# prototype2-only-bot-ground-plane.net
KiCad netlist of a schematic drawn in EAGLE
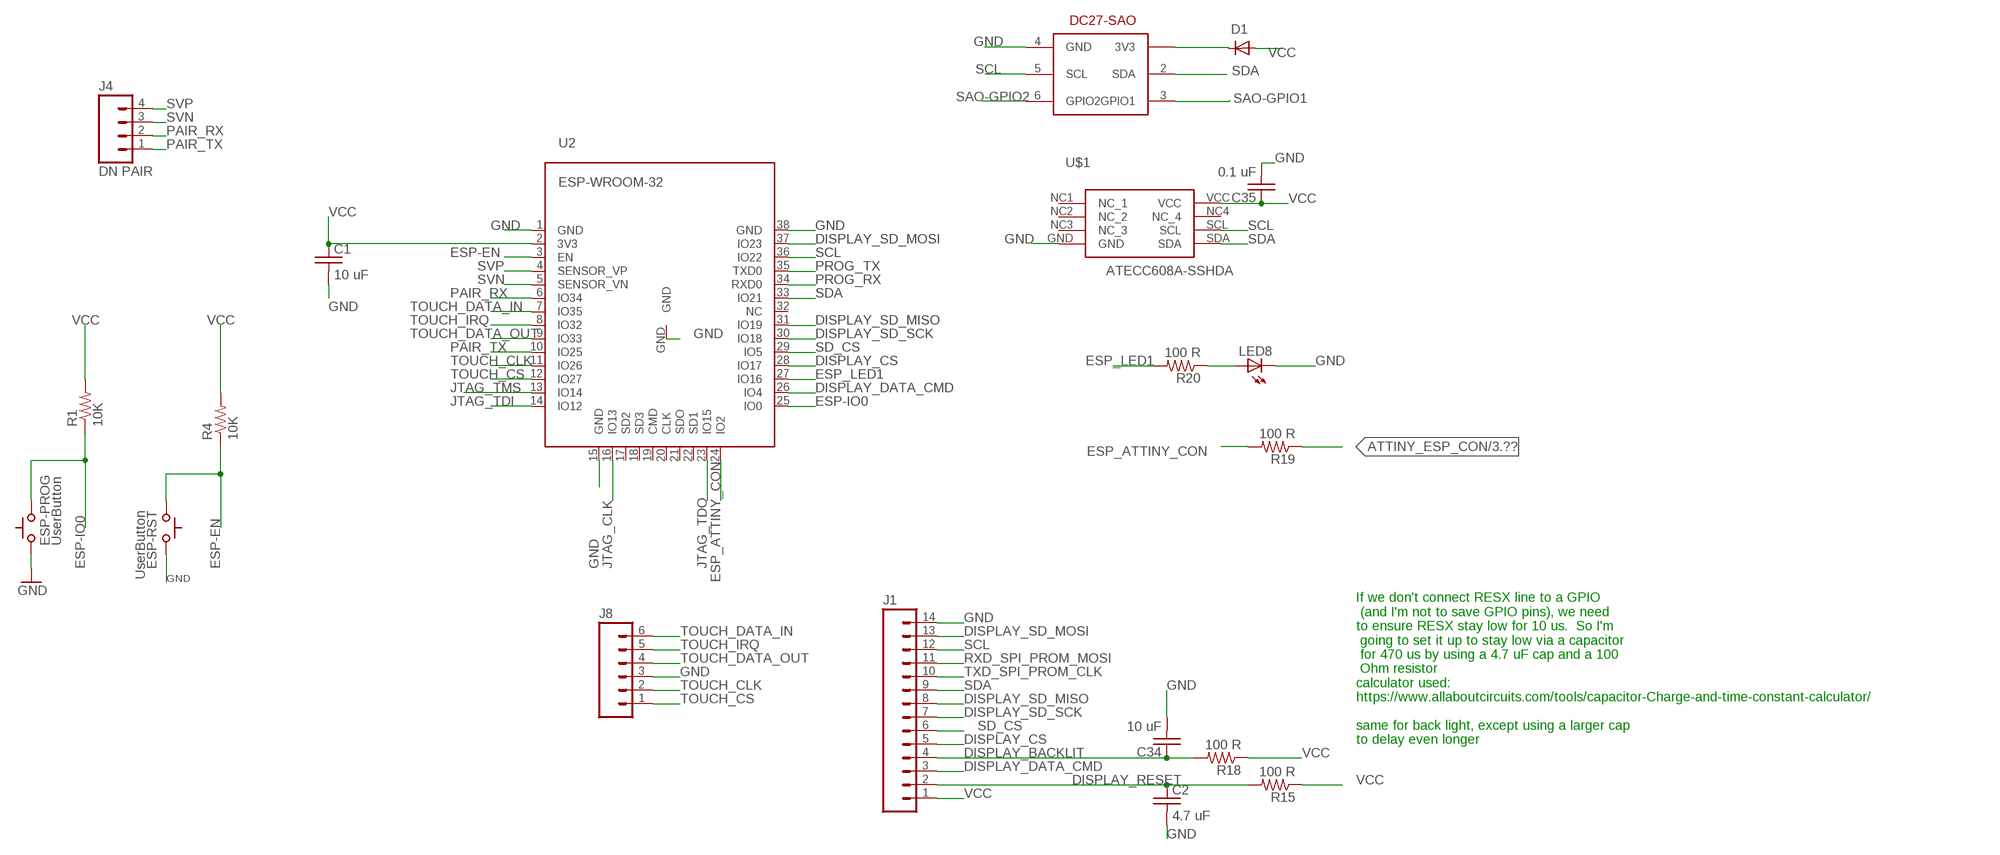
[diagram p0: schematic, sheet 1]
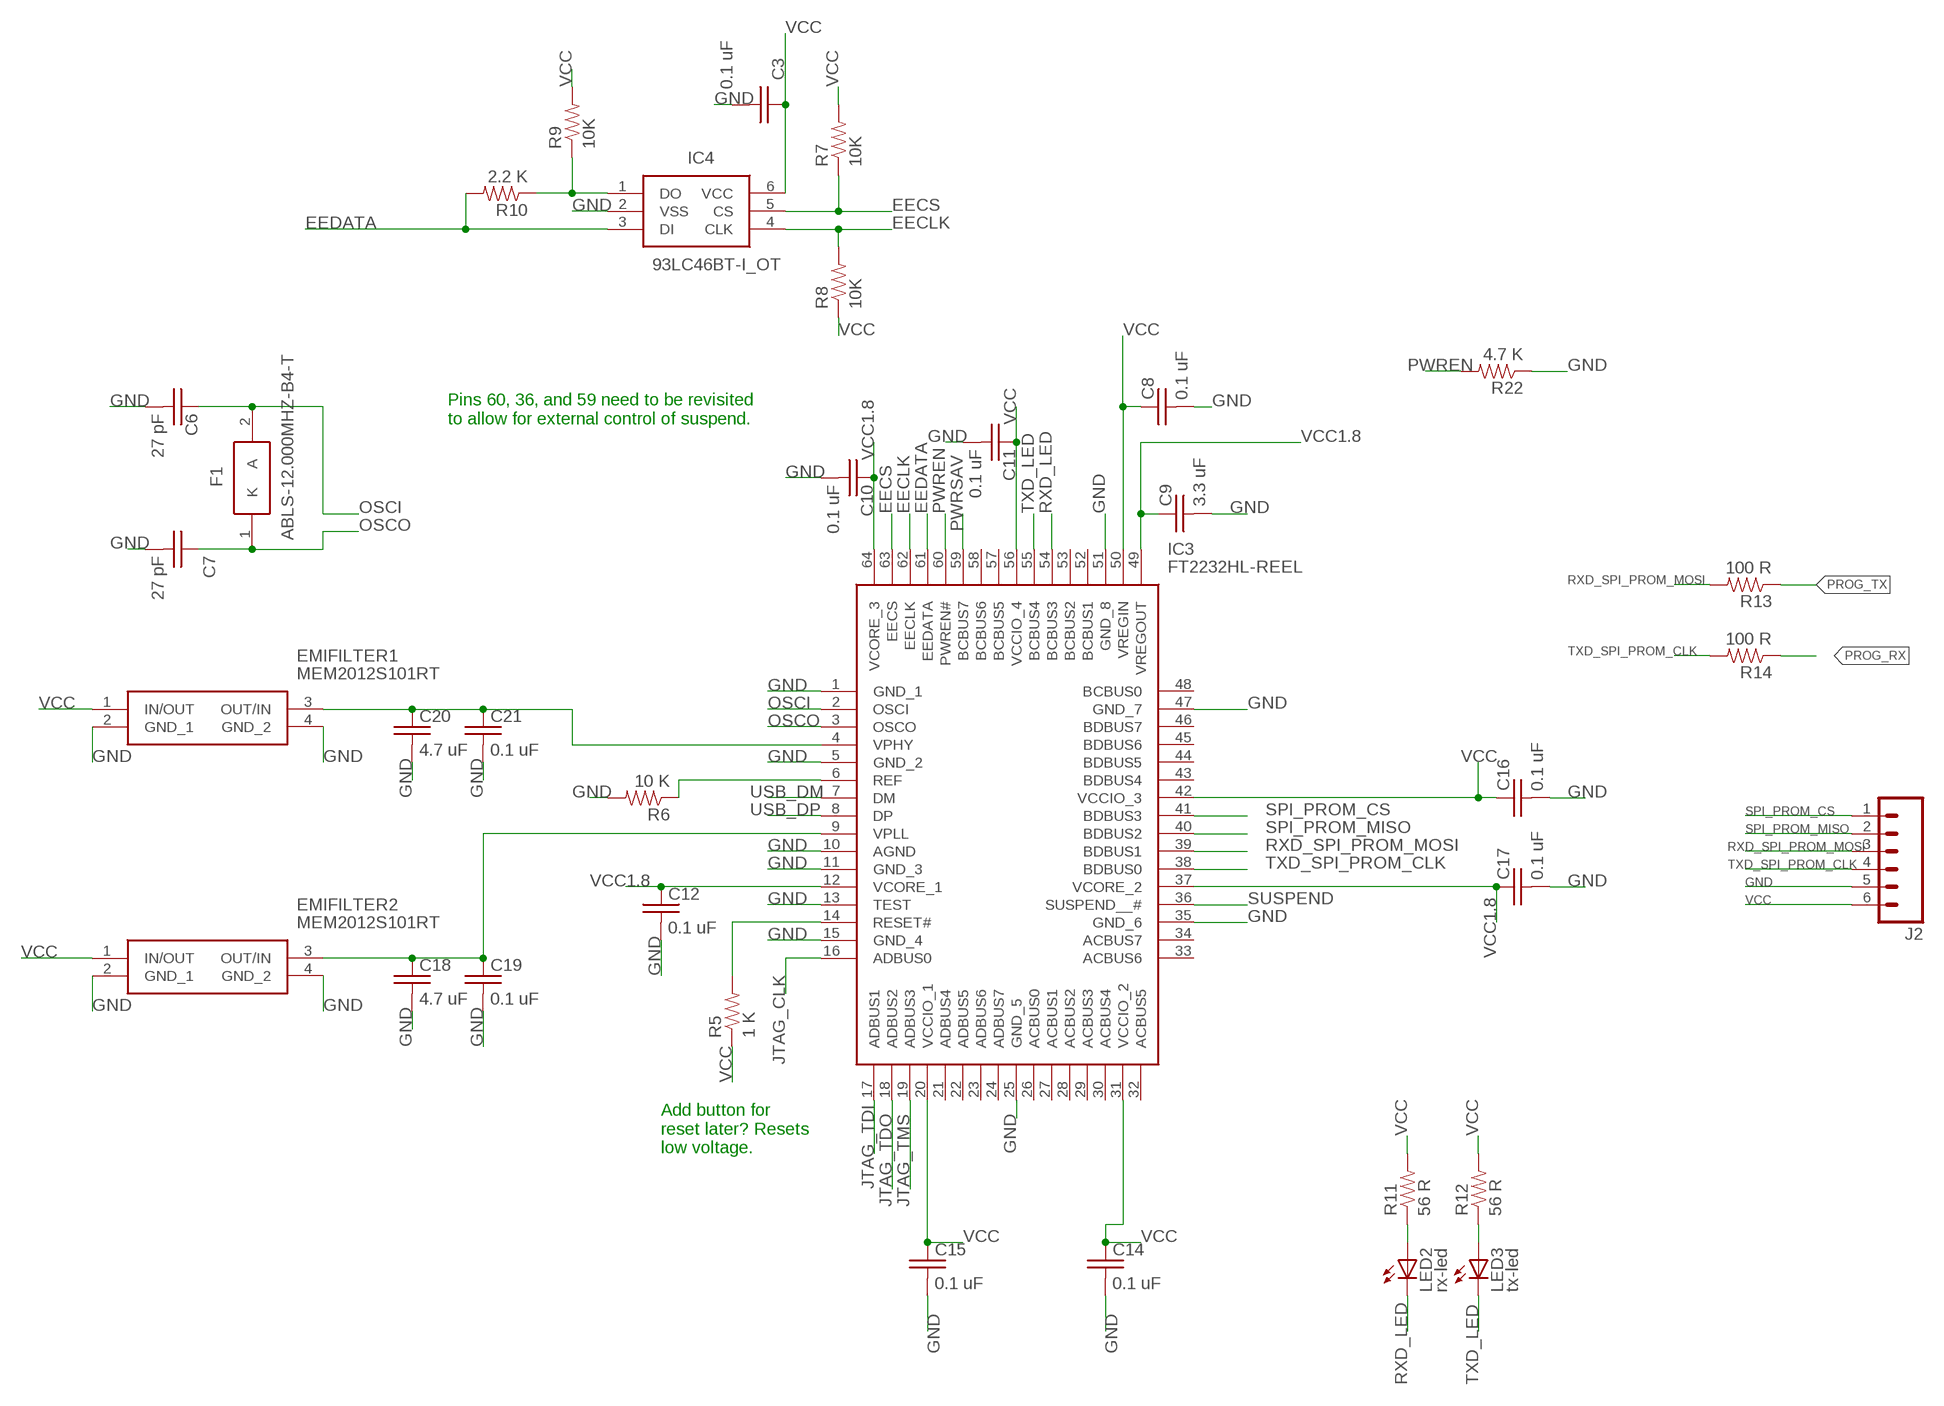
[diagram p1: schematic, sheet 2]
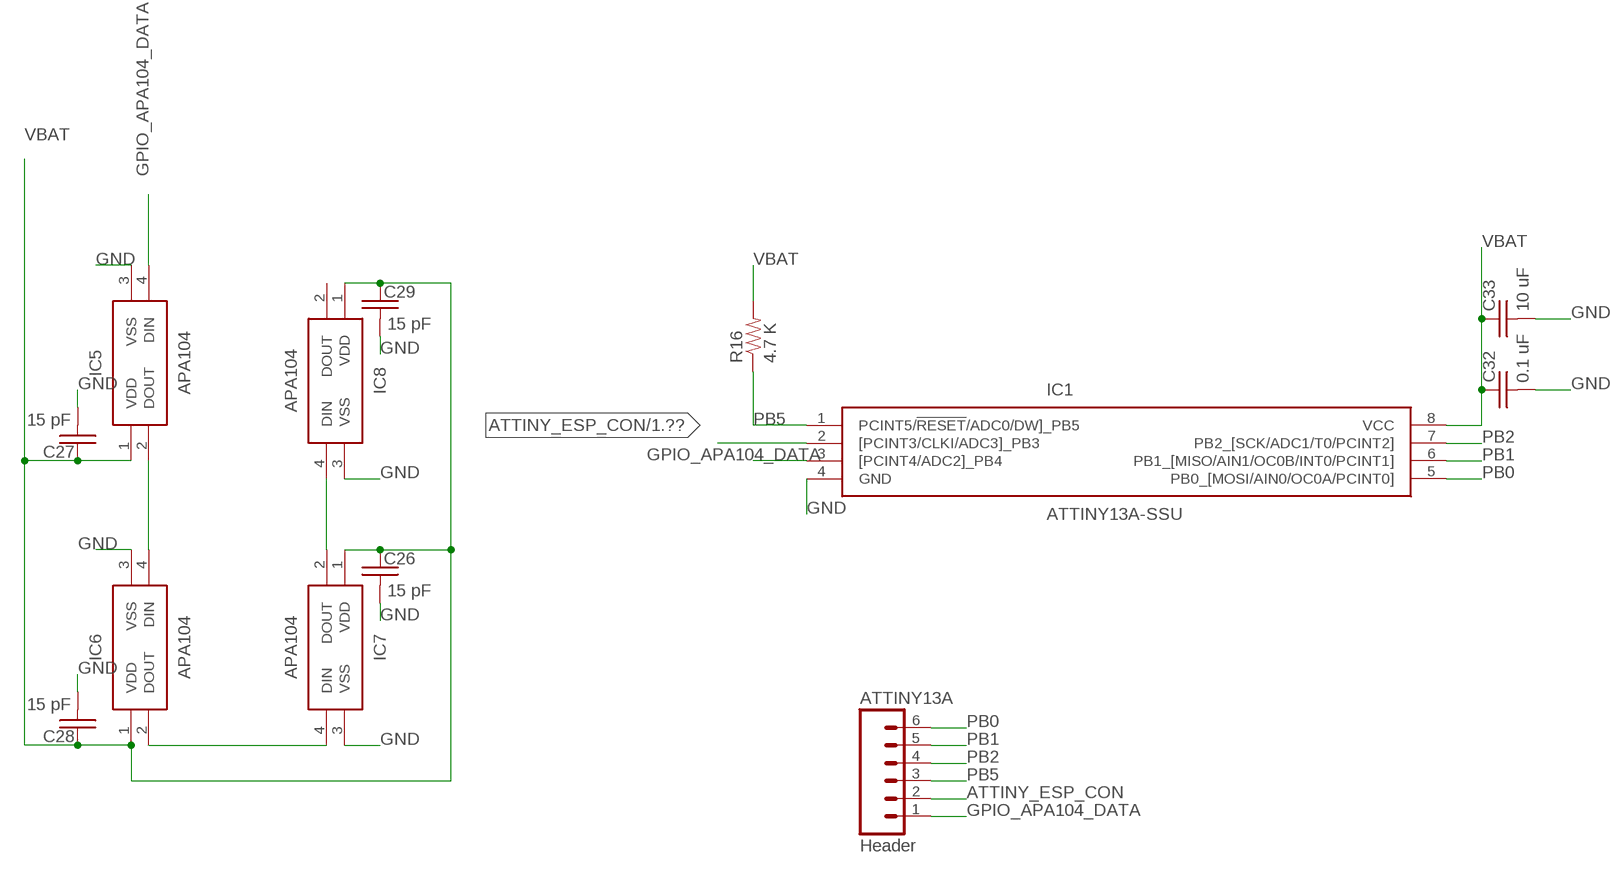
[diagram p2: schematic, sheet 3]
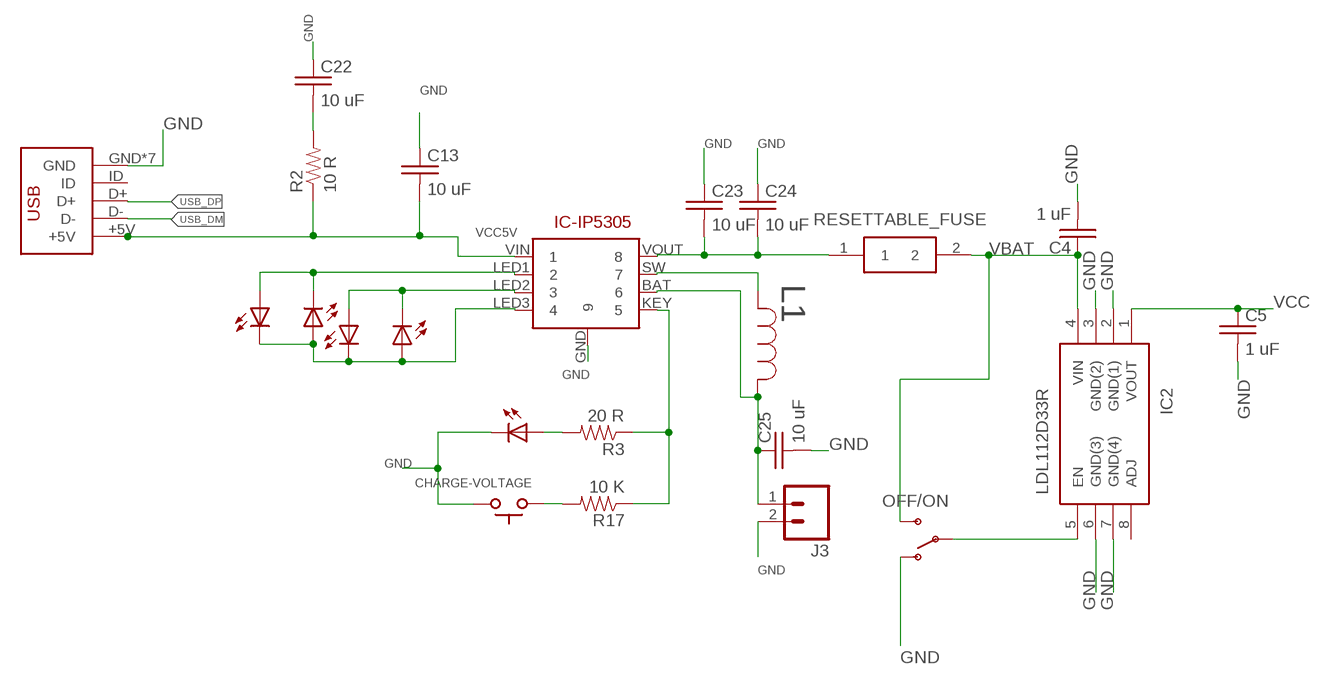
[diagram p3: schematic, sheet 4]
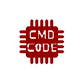
[diagram p4: schematic, sheet 5]

(export (version "E")
  (design (tool "Eeschema 10.0.6"))
  (components
    (comp (ref "C3")
      (value "0.1 uF")
      (footprint "eagle-import:C0805")
      (libsource (lib "eagle-import") (part "C-USC0805"))
    )
    (comp (ref "C6")
      (value "27 pF")
      (footprint "eagle-import:C0805")
      (libsource (lib "eagle-import") (part "C-USC0805"))
    )
    (comp (ref "C7")
      (value "27 pF")
      (footprint "eagle-import:C0805")
      (libsource (lib "eagle-import") (part "C-USC0805"))
    )
    (comp (ref "C8")
      (value "0.1 uF")
      (footprint "eagle-import:C0805")
      (libsource (lib "eagle-import") (part "C-USC0805"))
    )
    (comp (ref "C9")
      (value "3.3 uF")
      (footprint "eagle-import:C0805")
      (libsource (lib "eagle-import") (part "C-USC0805"))
    )
    (comp (ref "C10")
      (value "0.1 uF")
      (footprint "eagle-import:C0805")
      (libsource (lib "eagle-import") (part "C-USC0805"))
    )
    (comp (ref "C11")
      (value "0.1 uF")
      (footprint "eagle-import:C0805")
      (libsource (lib "eagle-import") (part "C-USC0805"))
    )
    (comp (ref "C12")
      (value "0.1 uF")
      (footprint "eagle-import:C0805")
      (libsource (lib "eagle-import") (part "C-USC0805"))
    )
    (comp (ref "C14")
      (value "0.1 uF")
      (footprint "eagle-import:C0805")
      (libsource (lib "eagle-import") (part "C-USC0805"))
    )
    (comp (ref "C15")
      (value "0.1 uF")
      (footprint "eagle-import:C0805")
      (libsource (lib "eagle-import") (part "C-USC0805"))
    )
    (comp (ref "C16")
      (value "0.1 uF")
      (footprint "eagle-import:C0805")
      (libsource (lib "eagle-import") (part "C-USC0805"))
    )
    (comp (ref "C17")
      (value "0.1 uF")
      (footprint "eagle-import:C0805")
      (libsource (lib "eagle-import") (part "C-USC0805"))
    )
    (comp (ref "C18")
      (value "4.7 uF")
      (footprint "eagle-import:C0805")
      (libsource (lib "eagle-import") (part "C-USC0805"))
    )
    (comp (ref "C19")
      (value "0.1 uF")
      (footprint "eagle-import:C0805")
      (libsource (lib "eagle-import") (part "C-USC0805"))
    )
    (comp (ref "C20")
      (value "4.7 uF")
      (footprint "eagle-import:C0805")
      (libsource (lib "eagle-import") (part "C-USC0805"))
    )
    (comp (ref "C21")
      (value "0.1 uF")
      (footprint "eagle-import:C0805")
      (libsource (lib "eagle-import") (part "C-USC0805"))
    )
    (comp (ref "EMIFILTER1")
      (value "MEM2012S101RT")
      (footprint "eagle-import:MEM2012S101RT")
      (libsource (lib "eagle-import") (part "MEM2012S101RT"))
    )
    (comp (ref "EMIFILTER2")
      (value "MEM2012S101RT")
      (footprint "eagle-import:MEM2012S101RT")
      (libsource (lib "eagle-import") (part "MEM2012S101RT"))
    )
    (comp (ref "F1")
      (value "ABLS-12.000MHZ-B4-T")
      (footprint "eagle-import:HC_49US-(AT49)_1")
      (fields
        (field (name "MOUSER_PART_NUMBER") "815-ABLS-12.0M-T")
        (field (name "RS_PART_NUMBER") "1710207")
      )
      (libsource (lib "eagle-import") (part "ABLS-12.000MHZ-B4-T"))
    )
    (comp (ref "IC3")
      (value "FT2232HL-REEL")
      (footprint "eagle-import:QFP50P1200X1200X160-64N")
      (fields (field (name "MOUSER_PART_NUMBER") "895-FT2232HL"))
      (libsource (lib "eagle-import") (part "FT2232HL-REEL"))
    )
    (comp (ref "IC4")
      (value "93LC46BT-I_OT")
      (footprint "eagle-import:SOT95P270X145-6N")
      (fields
        (field (name "MANUFACTURER_PART_NUMBER") "93LC46BT-I/OT")
        (field (name "MOUSER_PART_NUMBER") "579-93LC46BT-I/OT")
      )
      (libsource (lib "eagle-import") (part "93LC46BT-I_OT"))
    )
    (comp (ref "J2")
      (value "M06SILK_FEMALE_PTH")
      (footprint "eagle-import:1X06")
      (libsource (lib "eagle-import") (part "M06SILK_FEMALE_PTH"))
    )
    (comp (ref "LED2")
      (value "rx-led")
      (footprint "eagle-import:LED3MM")
      (libsource (lib "eagle-import") (part "LED3MM"))
    )
    (comp (ref "LED3")
      (value "tx-led")
      (footprint "eagle-import:LED3MM")
      (libsource (lib "eagle-import") (part "LED3MM"))
    )
    (comp (ref "R5")
      (value "1 K")
      (footprint "eagle-import:0805")
      (libsource (lib "eagle-import") (part "passives_RESISTOR0805-RES"))
    )
    (comp (ref "R6")
      (value "10 K")
      (footprint "eagle-import:0805")
      (libsource (lib "eagle-import") (part "passives_RESISTOR0805-RES"))
    )
    (comp (ref "R7")
      (value "10K")
      (footprint "eagle-import:0805")
      (libsource (lib "eagle-import") (part "passives_RESISTOR0805-RES"))
    )
    (comp (ref "R8")
      (value "10K")
      (footprint "eagle-import:0805")
      (libsource (lib "eagle-import") (part "passives_RESISTOR0805-RES"))
    )
    (comp (ref "R9")
      (value "10K")
      (footprint "eagle-import:0805")
      (libsource (lib "eagle-import") (part "passives_RESISTOR0805-RES"))
    )
    (comp (ref "R10")
      (value "2.2 K")
      (footprint "eagle-import:0805")
      (libsource (lib "eagle-import") (part "passives_RESISTOR0805-RES"))
    )
    (comp (ref "R11")
      (value "56 R")
      (footprint "eagle-import:0805")
      (libsource (lib "eagle-import") (part "passives_RESISTOR0805-RES"))
    )
    (comp (ref "R12")
      (value "56 R")
      (footprint "eagle-import:0805")
      (libsource (lib "eagle-import") (part "passives_RESISTOR0805-RES"))
    )
    (comp (ref "R13")
      (value "100 R")
      (footprint "eagle-import:0805")
      (libsource (lib "eagle-import") (part "passives_RESISTOR0805-RES"))
    )
    (comp (ref "R14")
      (value "100 R")
      (footprint "eagle-import:0805")
      (libsource (lib "eagle-import") (part "passives_RESISTOR0805-RES"))
    )
    (comp (ref "R22")
      (value "4.7 K")
      (footprint "eagle-import:0805")
      (libsource (lib "eagle-import") (part "passives_RESISTOR0805-RES"))
    )
    (comp (ref "C4")
      (value "1 uF")
      (footprint "eagle-import:C0805")
      (libsource (lib "eagle-import") (part "C-USC0805"))
    )
    (comp (ref "C5")
      (value "1 uF")
      (footprint "eagle-import:C0805")
      (libsource (lib "eagle-import") (part "C-USC0805"))
    )
    (comp (ref "C13")
      (value "10 uF")
      (footprint "eagle-import:C0805")
      (libsource (lib "eagle-import") (part "C-USC0805"))
    )
    (comp (ref "C22")
      (value "10 uF")
      (footprint "eagle-import:C0805")
      (libsource (lib "eagle-import") (part "C-USC0805"))
    )
    (comp (ref "C23")
      (value "10 uF")
      (footprint "eagle-import:C0805")
      (libsource (lib "eagle-import") (part "C-USC0805"))
    )
    (comp (ref "C24")
      (value "10 uF")
      (footprint "eagle-import:C0805")
      (libsource (lib "eagle-import") (part "C-USC0805"))
    )
    (comp (ref "C25")
      (value "10 uF")
      (footprint "eagle-import:C0805")
      (libsource (lib "eagle-import") (part "C-USC0805"))
    )
    (comp (ref "CHARGE-VOLTAGE")
      (value "UserButton")
      (footprint "eagle-import:TACTILE-2PIN-NARROW")
      (libsource (lib "eagle-import") (part "switches_SWITCH_TACTILETACTILE-2PIN-NARROW"))
    )
    (comp (ref "IC-IP5305")
      (value "IP5305ESOP8")
      (footprint "eagle-import:SOIC127P600X165-8")
      (libsource (lib "eagle-import") (part "IP5305ESOP8"))
    )
    (comp (ref "IC2")
      (value "LDL112D33R")
      (footprint "eagle-import:SOIC127P600X175-8N")
      (libsource (lib "eagle-import") (part "LDL112D33R"))
    )
    (comp (ref "J3")
      (value "M02PTH")
      (footprint "eagle-import:1X02")
      (libsource (lib "eagle-import") (part "M02PTH"))
    )
    (comp (ref "L1")
      (value "NRS4018T2R2MDGJ")
      (footprint "eagle-import:IND_TAIYO_NRS4018")
      (libsource (lib "eagle-import") (part "NRS4018T2R2MDGJ"))
    )
    (comp (ref "LED1")
      (value "LED3MM")
      (footprint "eagle-import:LED3MM")
      (libsource (lib "eagle-import") (part "LED3MM"))
    )
    (comp (ref "LED4")
      (value "LED3MM")
      (footprint "eagle-import:LED3MM")
      (libsource (lib "eagle-import") (part "LED3MM"))
    )
    (comp (ref "LED5")
      (value "LED3MM")
      (footprint "eagle-import:LED3MM")
      (libsource (lib "eagle-import") (part "LED3MM"))
    )
    (comp (ref "LED6")
      (value "LED3MM")
      (footprint "eagle-import:LED3MM")
      (libsource (lib "eagle-import") (part "LED3MM"))
    )
    (comp (ref "LED7")
      (value "LED3MM")
      (footprint "eagle-import:LED3MM")
      (libsource (lib "eagle-import") (part "LED3MM"))
    )
    (comp (ref "OFF/ON")
      (value "SWITCH-SPSTPTH_LOCK")
      (footprint "eagle-import:SWITCH-SPDT_LOCK.007S")
      (libsource (lib "eagle-import") (part "SWITCH-SPSTPTH_LOCK"))
    )
    (comp (ref "R2")
      (value "10 R")
      (footprint "eagle-import:0805")
      (libsource (lib "eagle-import") (part "passives_RESISTOR0805-RES"))
    )
    (comp (ref "R3")
      (value "20 R")
      (footprint "eagle-import:0805")
      (libsource (lib "eagle-import") (part "passives_RESISTOR0805-RES"))
    )
    (comp (ref "R17")
      (value "10 K")
      (footprint "eagle-import:0805")
      (libsource (lib "eagle-import") (part "passives_RESISTOR0805-RES"))
    )
    (comp (ref "RESETTABLE_FUSE")
      (value "0ZCJ0050FF2G")
      (footprint "eagle-import:FUSC3216X55N")
      (libsource (lib "eagle-import") (part "0ZCJ0050FF2G"))
    )
    (comp (ref "U$2")
      (value "DX4R005JJ2DX4R005JJ2")
      (footprint "eagle-import:DX4R005JJ2")
      (libsource (lib "eagle-import") (part "DX4R005JJ2DX4R005JJ2"))
    )
    (comp (ref "U$3")
      (value "CMD_C0DE_LOGOCMD_CODE_LOGO_TOP_COPPER")
      (footprint "eagle-import:CMD_C0DE_LOGO_TOP_COPPER")
      (libsource (lib "eagle-import") (part "CMD_C0DE_LOGOCMD_CODE_LOGO_TOP_COPPER"))
    )
    (comp (ref "ATTINY13A")
      (value "Header")
      (footprint "eagle-import:1X06")
      (libsource (lib "eagle-import") (part "M06SILK_FEMALE_PTH"))
    )
    (comp (ref "C26")
      (value "15 pF")
      (footprint "eagle-import:C0805")
      (libsource (lib "eagle-import") (part "C-USC0805"))
    )
    (comp (ref "C27")
      (value "15 pF")
      (footprint "eagle-import:C0805")
      (libsource (lib "eagle-import") (part "C-USC0805"))
    )
    (comp (ref "C28")
      (value "15 pF")
      (footprint "eagle-import:C0805")
      (libsource (lib "eagle-import") (part "C-USC0805"))
    )
    (comp (ref "C29")
      (value "15 pF")
      (footprint "eagle-import:C0805")
      (libsource (lib "eagle-import") (part "C-USC0805"))
    )
    (comp (ref "C32")
      (value "0.1 uF")
      (footprint "eagle-import:C0805")
      (libsource (lib "eagle-import") (part "C-USC0805"))
    )
    (comp (ref "C33")
      (value "10 uF")
      (footprint "eagle-import:C0805")
      (libsource (lib "eagle-import") (part "C-USC0805"))
    )
    (comp (ref "IC1")
      (value "ATTINY13A-SSU")
      (footprint "eagle-import:SOIC127P600X175-8N")
      (fields (field (name "MOUSER_PART_NUMBER") "556-ATTINY13A-SSU"))
      (libsource (lib "eagle-import") (part "ATTINY13A-SSU"))
    )
    (comp (ref "IC5")
      (value "APA104")
      (footprint "eagle-import:APA104")
      (libsource (lib "eagle-import") (part "APA104"))
    )
    (comp (ref "IC6")
      (value "APA104")
      (footprint "eagle-import:APA104")
      (libsource (lib "eagle-import") (part "APA104"))
    )
    (comp (ref "IC7")
      (value "APA104")
      (footprint "eagle-import:APA104")
      (libsource (lib "eagle-import") (part "APA104"))
    )
    (comp (ref "IC8")
      (value "APA104")
      (footprint "eagle-import:APA104")
      (libsource (lib "eagle-import") (part "APA104"))
    )
    (comp (ref "R16")
      (value "4.7 K")
      (footprint "eagle-import:0805")
      (libsource (lib "eagle-import") (part "passives_RESISTOR0805-RES"))
    )
    (comp (ref "C1")
      (value "10 uF")
      (footprint "eagle-import:C0805")
      (libsource (lib "eagle-import") (part "C-USC0805"))
    )
    (comp (ref "C2")
      (value "4.7 uF")
      (footprint "eagle-import:C0805")
      (libsource (lib "eagle-import") (part "C-USC0805"))
    )
    (comp (ref "C34")
      (value "10 uF")
      (footprint "eagle-import:C0805")
      (libsource (lib "eagle-import") (part "C-USC0805"))
    )
    (comp (ref "C35")
      (value "0.1 uF")
      (footprint "eagle-import:C0805")
      (libsource (lib "eagle-import") (part "C-USC0805"))
    )
    (comp (ref "D1")
      (value "DIODESMA")
      (footprint "eagle-import:SMA-DIODE")
      (libsource (lib "eagle-import") (part "DIODESMA"))
    )
    (comp (ref "ESP-PROG")
      (value "UserButton")
      (footprint "eagle-import:TACTILE-2PIN-NARROW")
      (libsource (lib "eagle-import") (part "SWITCH_TACTILETACTILE-2PIN-NARROW"))
    )
    (comp (ref "ESP-RST")
      (value "UserButton")
      (footprint "eagle-import:TACTILE-2PIN-NARROW")
      (libsource (lib "eagle-import") (part "SWITCH_TACTILETACTILE-2PIN-NARROW"))
    )
    (comp (ref "J1")
      (value "M14")
      (footprint "eagle-import:1X14")
      (libsource (lib "eagle-import") (part "M14"))
    )
    (comp (ref "J4")
      (value "DN PAIR")
      (footprint "eagle-import:1X04")
      (libsource (lib "eagle-import") (part "M04PTH"))
    )
    (comp (ref "J8")
      (value "M06NO_SILK_YES_STOP")
      (footprint "eagle-import:1X06_NO_SILK_YES_STOP")
      (libsource (lib "eagle-import") (part "M06NO_SILK_YES_STOP"))
    )
    (comp (ref "LED8")
      (value "LED3MM")
      (footprint "eagle-import:LED3MM")
      (libsource (lib "eagle-import") (part "LED3MM"))
    )
    (comp (ref "R1")
      (value "10K")
      (footprint "eagle-import:0805")
      (libsource (lib "eagle-import") (part "RESISTOR0805-RES"))
    )
    (comp (ref "R4")
      (value "10K")
      (footprint "eagle-import:0805")
      (libsource (lib "eagle-import") (part "RESISTOR0805-RES"))
    )
    (comp (ref "R15")
      (value "100 R")
      (footprint "eagle-import:0805")
      (libsource (lib "eagle-import") (part "RESISTOR0805-RES"))
    )
    (comp (ref "R18")
      (value "100 R")
      (footprint "eagle-import:0805")
      (libsource (lib "eagle-import") (part "RESISTOR0805-RES"))
    )
    (comp (ref "R19")
      (value "100 R")
      (footprint "eagle-import:0805")
      (libsource (lib "eagle-import") (part "RESISTOR0805-RES"))
    )
    (comp (ref "R20")
      (value "100 R")
      (footprint "eagle-import:0805")
      (libsource (lib "eagle-import") (part "RESISTOR0805-RES"))
    )
    (comp (ref "U$1")
      (value "ATECC608A-SSHDA")
      (footprint "eagle-import:8-SOIC")
      (libsource (lib "eagle-import") (part "ATECC608A-SSHDA"))
    )
    (comp (ref "U$4")
      (value "DC-27-SAO")
      (footprint "eagle-import:3X2")
      (libsource (lib "eagle-import") (part "DC-27-SAO"))
    )
    (comp (ref "U2")
      (value "ESP-WROOM-32")
      (footprint "eagle-import:ESP-WROOM-32")
      (libsource (lib "eagle-import") (part "ESP-WROOM-32"))
    )
  )
  (nets
    (net (code "1") (name "ATTINY_ESP_CON") (class "Default")
      (node (ref "ATTINY13A") (pin "2") (pinfunction "2_2") (pintype "passive"))
      (node (ref "IC1") (pin "2") (pinfunction "[PCINT3/CLKI/ADC3]_PB3_2") (pintype "input"))
      (node (ref "R19") (pin "1") (pinfunction "1_1") (pintype "passive"))
    )
    (net (code "2") (name "DISPLAY_BACKLIT") (class "Default")
      (node (ref "C34") (pin "1") (pinfunction "1_1") (pintype "passive"))
      (node (ref "J1") (pin "4") (pinfunction "4_4") (pintype "passive"))
      (node (ref "R18") (pin "2") (pinfunction "2_2") (pintype "passive"))
    )
    (net (code "3") (name "DISPLAY_CS") (class "Default")
      (node (ref "J1") (pin "5") (pinfunction "5_5") (pintype "passive"))
      (node (ref "U2") (pin "28") (pinfunction "IO17_28") (pintype "bidirectional"))
    )
    (net (code "4") (name "DISPLAY_DATA_CMD") (class "Default")
      (node (ref "J1") (pin "3") (pinfunction "3_3") (pintype "passive"))
      (node (ref "U2") (pin "26") (pinfunction "IO4_26") (pintype "bidirectional"))
    )
    (net (code "5") (name "DISPLAY_RESET") (class "Default")
      (node (ref "C2") (pin "1") (pinfunction "1_1") (pintype "passive"))
      (node (ref "J1") (pin "2") (pinfunction "2_2") (pintype "passive"))
      (node (ref "R15") (pin "2") (pinfunction "2_2") (pintype "passive"))
    )
    (net (code "6") (name "DISPLAY_SD_MISO") (class "Default")
      (node (ref "J1") (pin "8") (pinfunction "8_8") (pintype "passive"))
      (node (ref "U2") (pin "31") (pinfunction "IO19_31") (pintype "bidirectional"))
    )
    (net (code "7") (name "DISPLAY_SD_MOSI") (class "Default")
      (node (ref "J1") (pin "13") (pinfunction "13_13") (pintype "passive"))
      (node (ref "U2") (pin "37") (pinfunction "IO23_37") (pintype "bidirectional"))
    )
    (net (code "8") (name "DISPLAY_SD_SCK") (class "Default")
      (node (ref "J1") (pin "7") (pinfunction "7_7") (pintype "passive"))
      (node (ref "U2") (pin "30") (pinfunction "IO18_30") (pintype "bidirectional"))
    )
    (net (code "9") (name "EECLK") (class "Default")
      (node (ref "IC3") (pin "62") (pinfunction "EECLK_62") (pintype "bidirectional"))
      (node (ref "IC4") (pin "4") (pinfunction "CLK_4") (pintype "input"))
      (node (ref "R8") (pin "2") (pinfunction "2_2") (pintype "passive"))
    )
    (net (code "10") (name "EECS") (class "Default")
      (node (ref "IC3") (pin "63") (pinfunction "EECS_63") (pintype "bidirectional"))
      (node (ref "IC4") (pin "5") (pinfunction "CS_5") (pintype "input"))
      (node (ref "R7") (pin "1") (pinfunction "1_1") (pintype "passive"))
    )
    (net (code "11") (name "EEDATA") (class "Default")
      (node (ref "IC3") (pin "61") (pinfunction "EEDATA_61") (pintype "bidirectional"))
      (node (ref "IC4") (pin "3") (pinfunction "DI_3") (pintype "bidirectional"))
      (node (ref "R10") (pin "2") (pinfunction "2_2") (pintype "passive"))
    )
    (net (code "12") (name "ESP-EN") (class "Default")
      (node (ref "ESP-RST") (pin "P$2") (pinfunction "C_P$2") (pintype "passive"))
      (node (ref "R4") (pin "1") (pinfunction "1_1") (pintype "passive"))
      (node (ref "U2") (pin "3") (pinfunction "EN_3") (pintype "bidirectional"))
    )
    (net (code "13") (name "ESP-IO0") (class "Default")
      (node (ref "ESP-PROG") (pin "P$1") (pinfunction "A_P$1") (pintype "passive"))
      (node (ref "R1") (pin "1") (pinfunction "1_1") (pintype "passive"))
      (node (ref "U2") (pin "25") (pinfunction "IO0_25") (pintype "bidirectional"))
    )
    (net (code "14") (name "ESP_ATTINY_CON") (class "Default")
      (node (ref "R19") (pin "2") (pinfunction "2_2") (pintype "passive"))
      (node (ref "U2") (pin "24") (pinfunction "IO2_24") (pintype "bidirectional"))
    )
    (net (code "15") (name "ESP_LED1") (class "Default")
      (node (ref "R20") (pin "2") (pinfunction "2_2") (pintype "passive"))
      (node (ref "U2") (pin "27") (pinfunction "IO16_27") (pintype "bidirectional"))
    )
    (net (code "16") (name "GND") (class "Default")
      (node (ref "C1") (pin "2") (pinfunction "2_2") (pintype "passive"))
      (node (ref "C10") (pin "2") (pinfunction "2_2") (pintype "passive"))
      (node (ref "C11") (pin "2") (pinfunction "2_2") (pintype "passive"))
      (node (ref "C12") (pin "2") (pinfunction "2_2") (pintype "passive"))
      (node (ref "C13") (pin "1") (pinfunction "1_1") (pintype "passive"))
      (node (ref "C14") (pin "2") (pinfunction "2_2") (pintype "passive"))
      (node (ref "C15") (pin "2") (pinfunction "2_2") (pintype "passive"))
      (node (ref "C16") (pin "2") (pinfunction "2_2") (pintype "passive"))
      (node (ref "C17") (pin "2") (pinfunction "2_2") (pintype "passive"))
      (node (ref "C18") (pin "2") (pinfunction "2_2") (pintype "passive"))
      (node (ref "C19") (pin "2") (pinfunction "2_2") (pintype "passive"))
      (node (ref "C2") (pin "2") (pinfunction "2_2") (pintype "passive"))
      (node (ref "C20") (pin "2") (pinfunction "2_2") (pintype "passive"))
      (node (ref "C21") (pin "2") (pinfunction "2_2") (pintype "passive"))
      (node (ref "C22") (pin "1") (pinfunction "1_1") (pintype "passive"))
      (node (ref "C23") (pin "1") (pinfunction "1_1") (pintype "passive"))
      (node (ref "C24") (pin "1") (pinfunction "1_1") (pintype "passive"))
      (node (ref "C25") (pin "2") (pinfunction "2_2") (pintype "passive"))
      (node (ref "C26") (pin "2") (pinfunction "2_2") (pintype "passive"))
      (node (ref "C27") (pin "2") (pinfunction "2_2") (pintype "passive"))
      (node (ref "C28") (pin "2") (pinfunction "2_2") (pintype "passive"))
      (node (ref "C29") (pin "2") (pinfunction "2_2") (pintype "passive"))
      (node (ref "C3") (pin "2") (pinfunction "2_2") (pintype "passive"))
      (node (ref "C32") (pin "2") (pinfunction "2_2") (pintype "passive"))
      (node (ref "C33") (pin "2") (pinfunction "2_2") (pintype "passive"))
      (node (ref "C34") (pin "2") (pinfunction "2_2") (pintype "passive"))
      (node (ref "C35") (pin "2") (pinfunction "2_2") (pintype "passive"))
      (node (ref "C4") (pin "2") (pinfunction "2_2") (pintype "passive"))
      (node (ref "C5") (pin "2") (pinfunction "2_2") (pintype "passive"))
      (node (ref "C6") (pin "2") (pinfunction "2_2") (pintype "passive"))
      (node (ref "C7") (pin "2") (pinfunction "2_2") (pintype "passive"))
      (node (ref "C8") (pin "2") (pinfunction "2_2") (pintype "passive"))
      (node (ref "C9") (pin "2") (pinfunction "2_2") (pintype "passive"))
      (node (ref "CHARGE-VOLTAGE") (pin "P$1") (pinfunction "A_P$1") (pintype "passive"))
      (node (ref "EMIFILTER1") (pin "2") (pinfunction "GND_1_2") (pintype "bidirectional"))
      (node (ref "EMIFILTER1") (pin "4") (pinfunction "GND_2_4") (pintype "bidirectional"))
      (node (ref "EMIFILTER2") (pin "2") (pinfunction "GND_1_2") (pintype "bidirectional"))
      (node (ref "EMIFILTER2") (pin "4") (pinfunction "GND_2_4") (pintype "bidirectional"))
      (node (ref "ESP-PROG") (pin "P$2") (pinfunction "C_P$2") (pintype "passive"))
      (node (ref "ESP-RST") (pin "P$1") (pinfunction "A_P$1") (pintype "passive"))
      (node (ref "IC-IP5305") (pin "GND") (pinfunction "9_GND") (pintype "power_in"))
      (node (ref "IC1") (pin "4") (pinfunction "GND_4") (pintype "power_in"))
      (node (ref "IC2") (pin "2") (pinfunction "GND(1)_2") (pintype "bidirectional"))
      (node (ref "IC2") (pin "3") (pinfunction "GND(2)_3") (pintype "bidirectional"))
      (node (ref "IC2") (pin "6") (pinfunction "GND(3)_6") (pintype "bidirectional"))
      (node (ref "IC2") (pin "7") (pinfunction "GND(4)_7") (pintype "bidirectional"))
      (node (ref "IC3") (pin "1") (pinfunction "GND_1_1") (pintype "bidirectional"))
      (node (ref "IC3") (pin "10") (pinfunction "AGND_10") (pintype "bidirectional"))
      (node (ref "IC3") (pin "11") (pinfunction "GND_3_11") (pintype "bidirectional"))
      (node (ref "IC3") (pin "13") (pinfunction "TEST_13") (pintype "bidirectional"))
      (node (ref "IC3") (pin "15") (pinfunction "GND_4_15") (pintype "bidirectional"))
      (node (ref "IC3") (pin "25") (pinfunction "GND_5_25") (pintype "bidirectional"))
      (node (ref "IC3") (pin "35") (pinfunction "GND_6_35") (pintype "bidirectional"))
      (node (ref "IC3") (pin "47") (pinfunction "GND_7_47") (pintype "bidirectional"))
      (node (ref "IC3") (pin "5") (pinfunction "GND_2_5") (pintype "bidirectional"))
      (node (ref "IC3") (pin "51") (pinfunction "GND_8_51") (pintype "bidirectional"))
      (node (ref "IC4") (pin "2") (pinfunction "VSS_2") (pintype "power_in"))
      (node (ref "IC5") (pin "3") (pinfunction "VSS_3") (pintype "power_in"))
      (node (ref "IC6") (pin "3") (pinfunction "VSS_3") (pintype "power_in"))
      (node (ref "IC7") (pin "3") (pinfunction "VSS_3") (pintype "power_in"))
      (node (ref "IC8") (pin "3") (pinfunction "VSS_3") (pintype "power_in"))
      (node (ref "J1") (pin "14") (pinfunction "14_14") (pintype "passive"))
      (node (ref "J2") (pin "5") (pinfunction "5_5") (pintype "passive"))
      (node (ref "J3") (pin "2") (pinfunction "2_2") (pintype "passive"))
      (node (ref "J8") (pin "3") (pinfunction "3_3") (pintype "passive"))
      (node (ref "LED7") (pin "K") (pinfunction "C_K") (pintype "output"))
      (node (ref "LED8") (pin "K") (pinfunction "C_K") (pintype "output"))
      (node (ref "OFF/ON") (pin "1") (pinfunction "O_1") (pintype "passive"))
      (node (ref "R22") (pin "1") (pinfunction "1_1") (pintype "passive"))
      (node (ref "R6") (pin "2") (pinfunction "2_2") (pintype "passive"))
      (node (ref "U$1") (pin "GND") (pinfunction "GND_GND") (pintype "power_in"))
      (node (ref "U$2") (pin "GND") (pinfunction "GND_GND") (pintype "bidirectional"))
      (node (ref "U$2") (pin "P$10") (pinfunction "GND_P$10") (pintype "bidirectional"))
      (node (ref "U$2") (pin "P$11") (pinfunction "GND_P$11") (pintype "bidirectional"))
      (node (ref "U$2") (pin "P$6") (pinfunction "GND_P$6") (pintype "bidirectional"))
      (node (ref "U$2") (pin "P$7") (pinfunction "GND_P$7") (pintype "bidirectional"))
      (node (ref "U$2") (pin "P$8") (pinfunction "GND_P$8") (pintype "bidirectional"))
      (node (ref "U$2") (pin "P$9") (pinfunction "GND_P$9") (pintype "bidirectional"))
      (node (ref "U$4") (pin "4") (pinfunction "GND_4") (pintype "power_in"))
      (node (ref "U2") (pin "1") (pinfunction "GND_1") (pintype "bidirectional"))
      (node (ref "U2") (pin "15") (pinfunction "GND_15") (pintype "bidirectional"))
      (node (ref "U2") (pin "38") (pinfunction "GND_38") (pintype "bidirectional"))
      (node (ref "U2") (pin "GND") (pinfunction "GND_GND") (pintype "bidirectional"))
    )
    (net (code "17") (name "GPIO_APA104_DATA") (class "Default")
      (node (ref "ATTINY13A") (pin "1") (pinfunction "1_1") (pintype "passive"))
      (node (ref "IC1") (pin "3") (pinfunction "[PCINT4/ADC2]_PB4_3") (pintype "input"))
      (node (ref "IC5") (pin "4") (pinfunction "DIN_4") (pintype "input"))
    )
    (net (code "18") (name "JTAG_CLK") (class "Default")
      (node (ref "IC3") (pin "16") (pinfunction "ADBUS0_16") (pintype "bidirectional"))
      (node (ref "U2") (pin "16") (pinfunction "IO13_16") (pintype "bidirectional"))
    )
    (net (code "19") (name "JTAG_TDI") (class "Default")
      (node (ref "IC3") (pin "17") (pinfunction "ADBUS1_17") (pintype "bidirectional"))
      (node (ref "U2") (pin "14") (pinfunction "IO12_14") (pintype "bidirectional"))
    )
    (net (code "20") (name "JTAG_TDO") (class "Default")
      (node (ref "IC3") (pin "18") (pinfunction "ADBUS2_18") (pintype "bidirectional"))
      (node (ref "U2") (pin "23") (pinfunction "IO15_23") (pintype "bidirectional"))
    )
    (net (code "21") (name "JTAG_TMS") (class "Default")
      (node (ref "IC3") (pin "19") (pinfunction "ADBUS3_19") (pintype "bidirectional"))
      (node (ref "U2") (pin "13") (pinfunction "IO14_13") (pintype "bidirectional"))
    )
    (net (code "22") (name "Net-(C22-Pad2)") (class "Default")
      (node (ref "C22") (pin "2") (pinfunction "2_2") (pintype "passive"))
      (node (ref "R2") (pin "2") (pinfunction "2_2") (pintype "passive"))
    )
    (net (code "23") (name "Net-(CHARGE-VOLTAGE-C)") (class "Default")
      (node (ref "CHARGE-VOLTAGE") (pin "P$2") (pinfunction "C_P$2") (pintype "passive"))
      (node (ref "R17") (pin "2") (pinfunction "2_2") (pintype "passive"))
    )
    (net (code "24") (name "Net-(EMIFILTER1-OUT{slash}IN)") (class "Default")
      (node (ref "C20") (pin "1") (pinfunction "1_1") (pintype "passive"))
      (node (ref "C21") (pin "1") (pinfunction "1_1") (pintype "passive"))
      (node (ref "EMIFILTER1") (pin "3") (pinfunction "OUT/IN_3") (pintype "bidirectional"))
      (node (ref "IC3") (pin "4") (pinfunction "VPHY_4") (pintype "bidirectional"))
    )
    (net (code "25") (name "Net-(EMIFILTER2-OUT{slash}IN)") (class "Default")
      (node (ref "C18") (pin "1") (pinfunction "1_1") (pintype "passive"))
      (node (ref "C19") (pin "1") (pinfunction "1_1") (pintype "passive"))
      (node (ref "EMIFILTER2") (pin "3") (pinfunction "OUT/IN_3") (pintype "bidirectional"))
      (node (ref "IC3") (pin "9") (pinfunction "VPLL_9") (pintype "bidirectional"))
    )
    (net (code "26") (name "Net-(IC-IP5305-2)") (class "Default")
      (node (ref "IC-IP5305") (pin "LED1") (pinfunction "2_LED1") (pintype "output"))
      (node (ref "LED1") (pin "A") (pinfunction "A_A") (pintype "input"))
      (node (ref "LED4") (pin "K") (pinfunction "C_K") (pintype "output"))
    )
    (net (code "27") (name "Net-(IC-IP5305-3)") (class "Default")
      (node (ref "IC-IP5305") (pin "LED2") (pinfunction "3_LED2") (pintype "output"))
      (node (ref "LED5") (pin "A") (pinfunction "A_A") (pintype "input"))
      (node (ref "LED6") (pin "K") (pinfunction "C_K") (pintype "output"))
    )
    (net (code "28") (name "Net-(IC-IP5305-4)") (class "Default")
      (node (ref "IC-IP5305") (pin "LED3") (pinfunction "4_LED3") (pintype "output"))
      (node (ref "LED1") (pin "K") (pinfunction "C_K") (pintype "output"))
      (node (ref "LED4") (pin "A") (pinfunction "A_A") (pintype "input"))
      (node (ref "LED5") (pin "K") (pinfunction "C_K") (pintype "output"))
      (node (ref "LED6") (pin "A") (pinfunction "A_A") (pintype "input"))
    )
    (net (code "29") (name "Net-(IC-IP5305-5)") (class "Default")
      (node (ref "IC-IP5305") (pin "KEY") (pinfunction "5_KEY") (pintype "bidirectional"))
      (node (ref "R17") (pin "1") (pinfunction "1_1") (pintype "passive"))
      (node (ref "R3") (pin "1") (pinfunction "1_1") (pintype "passive"))
    )
    (net (code "30") (name "Net-(IC-IP5305-6)") (class "Default")
      (node (ref "C25") (pin "1") (pinfunction "1_1") (pintype "passive"))
      (node (ref "IC-IP5305") (pin "BAT") (pinfunction "6_BAT") (pintype "bidirectional"))
      (node (ref "J3") (pin "1") (pinfunction "1_1") (pintype "passive"))
      (node (ref "L1") (pin "1") (pinfunction "1_1") (pintype "passive"))
    )
    (net (code "31") (name "Net-(IC-IP5305-7)") (class "Default")
      (node (ref "IC-IP5305") (pin "SW") (pinfunction "7_SW") (pintype "bidirectional"))
      (node (ref "L1") (pin "2") (pinfunction "2_2") (pintype "passive"))
    )
    (net (code "32") (name "Net-(IC-IP5305-8)") (class "Default")
      (node (ref "C23") (pin "2") (pinfunction "2_2") (pintype "passive"))
      (node (ref "C24") (pin "2") (pinfunction "2_2") (pintype "passive"))
      (node (ref "IC-IP5305") (pin "VOUT") (pinfunction "8_VOUT") (pintype "bidirectional"))
      (node (ref "RESETTABLE_FUSE") (pin "1") (pinfunction "1_1") (pintype "passive"))
    )
    (net (code "33") (name "Net-(IC2-EN)") (class "Default")
      (node (ref "IC2") (pin "5") (pinfunction "EN_5") (pintype "bidirectional"))
      (node (ref "OFF/ON") (pin "2") (pinfunction "P_2") (pintype "passive"))
    )
    (net (code "34") (name "Net-(IC3-REF)") (class "Default")
      (node (ref "IC3") (pin "6") (pinfunction "REF_6") (pintype "bidirectional"))
      (node (ref "R6") (pin "1") (pinfunction "1_1") (pintype "passive"))
    )
    (net (code "35") (name "Net-(IC3-RESET#)") (class "Default")
      (node (ref "IC3") (pin "14") (pinfunction "RESET#_14") (pintype "bidirectional"))
      (node (ref "R5") (pin "2") (pinfunction "2_2") (pintype "passive"))
    )
    (net (code "36") (name "Net-(IC4-DO)") (class "Default")
      (node (ref "IC4") (pin "1") (pinfunction "DO_1") (pintype "bidirectional"))
      (node (ref "R10") (pin "1") (pinfunction "1_1") (pintype "passive"))
      (node (ref "R9") (pin "1") (pinfunction "1_1") (pintype "passive"))
    )
    (net (code "37") (name "Net-(IC5-DOUT)") (class "Default")
      (node (ref "IC5") (pin "2") (pinfunction "DOUT_2") (pintype "output"))
      (node (ref "IC6") (pin "4") (pinfunction "DIN_4") (pintype "input"))
    )
    (net (code "38") (name "Net-(IC6-DOUT)") (class "Default")
      (node (ref "IC6") (pin "2") (pinfunction "DOUT_2") (pintype "output"))
      (node (ref "IC7") (pin "4") (pinfunction "DIN_4") (pintype "input"))
    )
    (net (code "39") (name "Net-(IC7-DOUT)") (class "Default")
      (node (ref "IC7") (pin "2") (pinfunction "DOUT_2") (pintype "output"))
      (node (ref "IC8") (pin "4") (pinfunction "DIN_4") (pintype "input"))
    )
    (net (code "40") (name "Net-(LED2-PadA)") (class "Default")
      (node (ref "LED2") (pin "A") (pinfunction "A_A") (pintype "input"))
      (node (ref "R11") (pin "1") (pinfunction "1_1") (pintype "passive"))
    )
    (net (code "41") (name "Net-(LED3-PadA)") (class "Default")
      (node (ref "LED3") (pin "A") (pinfunction "A_A") (pintype "input"))
      (node (ref "R12") (pin "1") (pinfunction "1_1") (pintype "passive"))
    )
    (net (code "42") (name "Net-(LED7-PadA)") (class "Default")
      (node (ref "LED7") (pin "A") (pinfunction "A_A") (pintype "input"))
      (node (ref "R3") (pin "2") (pinfunction "2_2") (pintype "passive"))
    )
    (net (code "43") (name "Net-(LED8-PadA)") (class "Default")
      (node (ref "LED8") (pin "A") (pinfunction "A_A") (pintype "input"))
      (node (ref "R20") (pin "1") (pinfunction "1_1") (pintype "passive"))
    )
    (net (code "44") (name "Net-(U$4-3V3)") (class "Default")
      (node (ref "D1") (pin "C") (pinfunction "C_C") (pintype "passive"))
      (node (ref "U$4") (pin "1") (pinfunction "3V3_1") (pintype "power_in"))
    )
    (net (code "45") (name "OSCI") (class "Default")
      (node (ref "C6") (pin "1") (pinfunction "1_1") (pintype "passive"))
      (node (ref "F1") (pin "2") (pinfunction "A_2") (pintype "bidirectional"))
      (node (ref "IC3") (pin "2") (pinfunction "OSCI_2") (pintype "bidirectional"))
    )
    (net (code "46") (name "OSCO") (class "Default")
      (node (ref "C7") (pin "1") (pinfunction "1_1") (pintype "passive"))
      (node (ref "F1") (pin "1") (pinfunction "K_1") (pintype "bidirectional"))
      (node (ref "IC3") (pin "3") (pinfunction "OSCO_3") (pintype "bidirectional"))
    )
    (net (code "47") (name "PAIR_RX") (class "Default")
      (node (ref "J4") (pin "2") (pinfunction "2_2") (pintype "passive"))
      (node (ref "U2") (pin "6") (pinfunction "IO34_6") (pintype "bidirectional"))
    )
    (net (code "48") (name "PAIR_TX") (class "Default")
      (node (ref "J4") (pin "1") (pinfunction "1_1") (pintype "passive"))
      (node (ref "U2") (pin "10") (pinfunction "IO25_10") (pintype "bidirectional"))
    )
    (net (code "49") (name "PB0") (class "Default")
      (node (ref "ATTINY13A") (pin "6") (pinfunction "6_6") (pintype "passive"))
      (node (ref "IC1") (pin "5") (pinfunction "PB0_[MOSI/AIN0/OC0A/PCINT0]_5") (pintype "input"))
    )
    (net (code "50") (name "PB1") (class "Default")
      (node (ref "ATTINY13A") (pin "5") (pinfunction "5_5") (pintype "passive"))
      (node (ref "IC1") (pin "6") (pinfunction "PB1_[MISO/AIN1/OC0B/INT0/PCINT1]_6") (pintype "input"))
    )
    (net (code "51") (name "PB2") (class "Default")
      (node (ref "ATTINY13A") (pin "4") (pinfunction "4_4") (pintype "passive"))
      (node (ref "IC1") (pin "7") (pinfunction "PB2_[SCK/ADC1/T0/PCINT2]_7") (pintype "input"))
    )
    (net (code "52") (name "PB5") (class "Default")
      (node (ref "ATTINY13A") (pin "3") (pinfunction "3_3") (pintype "passive"))
      (node (ref "IC1") (pin "1") (pinfunction "PCINT5/~{RESET}/ADC0/DW]_PB5_1") (pintype "input"))
      (node (ref "R16") (pin "1") (pinfunction "1_1") (pintype "passive"))
    )
    (net (code "53") (name "PROG_RX") (class "Default")
      (node (ref "R14") (pin "1") (pinfunction "1_1") (pintype "passive"))
      (node (ref "U2") (pin "34") (pinfunction "RXD0_34") (pintype "bidirectional"))
    )
    (net (code "54") (name "PROG_TX") (class "Default")
      (node (ref "R13") (pin "1") (pinfunction "1_1") (pintype "passive"))
      (node (ref "U2") (pin "35") (pinfunction "TXD0_35") (pintype "bidirectional"))
    )
    (net (code "55") (name "PWREN") (class "Default")
      (node (ref "IC3") (pin "60") (pinfunction "PWREN#_60") (pintype "bidirectional"))
      (node (ref "R22") (pin "2") (pinfunction "2_2") (pintype "passive"))
    )
    (net (code "56") (name "PWRSAV") (class "Default")
      (node (ref "IC3") (pin "59") (pinfunction "BCBUS7_59") (pintype "bidirectional"))
    )
    (net (code "57") (name "RXD_LED") (class "Default")
      (node (ref "IC3") (pin "54") (pinfunction "BCBUS3_54") (pintype "bidirectional"))
      (node (ref "LED2") (pin "K") (pinfunction "C_K") (pintype "output"))
    )
    (net (code "58") (name "RXD_SPI_PROM_MOSI") (class "Default")
      (node (ref "IC3") (pin "39") (pinfunction "BDBUS1_39") (pintype "bidirectional"))
      (node (ref "J1") (pin "11") (pinfunction "11_11") (pintype "passive"))
      (node (ref "J2") (pin "3") (pinfunction "3_3") (pintype "passive"))
      (node (ref "R13") (pin "2") (pinfunction "2_2") (pintype "passive"))
    )
    (net (code "59") (name "SAO-GPIO1") (class "Default")
      (node (ref "U$4") (pin "3") (pinfunction "GPIO1_3") (pintype "bidirectional"))
    )
    (net (code "60") (name "SAO-GPIO2") (class "Default")
      (node (ref "U$4") (pin "6") (pinfunction "GPIO2_6") (pintype "bidirectional"))
    )
    (net (code "61") (name "SCL") (class "Default")
      (node (ref "J1") (pin "12") (pinfunction "12_12") (pintype "passive"))
      (node (ref "U$1") (pin "SCL") (pinfunction "SCL_SCL") (pintype "bidirectional"))
      (node (ref "U$4") (pin "5") (pinfunction "SCL_5") (pintype "bidirectional"))
      (node (ref "U2") (pin "36") (pinfunction "IO22_36") (pintype "bidirectional"))
    )
    (net (code "62") (name "SDA") (class "Default")
      (node (ref "J1") (pin "9") (pinfunction "9_9") (pintype "passive"))
      (node (ref "U$1") (pin "SDA") (pinfunction "SDA_SDA") (pintype "bidirectional"))
      (node (ref "U$4") (pin "2") (pinfunction "SDA_2") (pintype "bidirectional"))
      (node (ref "U2") (pin "33") (pinfunction "IO21_33") (pintype "bidirectional"))
    )
    (net (code "63") (name "SD_CS") (class "Default")
      (node (ref "J1") (pin "6") (pinfunction "6_6") (pintype "passive"))
      (node (ref "U2") (pin "29") (pinfunction "IO5_29") (pintype "bidirectional"))
    )
    (net (code "64") (name "SPI_PROM_CS") (class "Default")
      (node (ref "IC3") (pin "41") (pinfunction "BDBUS3_41") (pintype "bidirectional"))
      (node (ref "J2") (pin "1") (pinfunction "1_1") (pintype "passive"))
    )
    (net (code "65") (name "SPI_PROM_MISO") (class "Default")
      (node (ref "IC3") (pin "40") (pinfunction "BDBUS2_40") (pintype "bidirectional"))
      (node (ref "J2") (pin "2") (pinfunction "2_2") (pintype "passive"))
    )
    (net (code "66") (name "SUSPEND") (class "Default")
      (node (ref "IC3") (pin "36") (pinfunction "SUSPEND__#_36") (pintype "bidirectional"))
    )
    (net (code "67") (name "SVN") (class "Default")
      (node (ref "J4") (pin "3") (pinfunction "3_3") (pintype "passive"))
      (node (ref "U2") (pin "5") (pinfunction "SENSOR_VN_5") (pintype "bidirectional"))
    )
    (net (code "68") (name "SVP") (class "Default")
      (node (ref "J4") (pin "4") (pinfunction "4_4") (pintype "passive"))
      (node (ref "U2") (pin "4") (pinfunction "SENSOR_VP_4") (pintype "bidirectional"))
    )
    (net (code "69") (name "TOUCH_CLK") (class "Default")
      (node (ref "J8") (pin "2") (pinfunction "2_2") (pintype "passive"))
      (node (ref "U2") (pin "11") (pinfunction "IO26_11") (pintype "bidirectional"))
    )
    (net (code "70") (name "TOUCH_CS") (class "Default")
      (node (ref "J8") (pin "1") (pinfunction "1_1") (pintype "passive"))
      (node (ref "U2") (pin "12") (pinfunction "IO27_12") (pintype "bidirectional"))
    )
    (net (code "71") (name "TOUCH_DATA_IN") (class "Default")
      (node (ref "J8") (pin "6") (pinfunction "6_6") (pintype "passive"))
      (node (ref "U2") (pin "7") (pinfunction "IO35_7") (pintype "bidirectional"))
    )
    (net (code "72") (name "TOUCH_DATA_OUT") (class "Default")
      (node (ref "J8") (pin "4") (pinfunction "4_4") (pintype "passive"))
      (node (ref "U2") (pin "9") (pinfunction "IO33_9") (pintype "bidirectional"))
    )
    (net (code "73") (name "TOUCH_IRQ") (class "Default")
      (node (ref "J8") (pin "5") (pinfunction "5_5") (pintype "passive"))
      (node (ref "U2") (pin "8") (pinfunction "IO32_8") (pintype "bidirectional"))
    )
    (net (code "74") (name "TXD_LED") (class "Default")
      (node (ref "IC3") (pin "55") (pinfunction "BCBUS4_55") (pintype "bidirectional"))
      (node (ref "LED3") (pin "K") (pinfunction "C_K") (pintype "output"))
    )
    (net (code "75") (name "TXD_SPI_PROM_CLK") (class "Default")
      (node (ref "IC3") (pin "38") (pinfunction "BDBUS0_38") (pintype "bidirectional"))
      (node (ref "J1") (pin "10") (pinfunction "10_10") (pintype "passive"))
      (node (ref "J2") (pin "4") (pinfunction "4_4") (pintype "passive"))
      (node (ref "R14") (pin "2") (pinfunction "2_2") (pintype "passive"))
    )
    (net (code "76") (name "USB_DM") (class "Default")
      (node (ref "IC3") (pin "7") (pinfunction "DM_7") (pintype "bidirectional"))
      (node (ref "U$2") (pin "D-") (pinfunction "D-_D-") (pintype "bidirectional"))
    )
    (net (code "77") (name "USB_DP") (class "Default")
      (node (ref "IC3") (pin "8") (pinfunction "DP_8") (pintype "bidirectional"))
      (node (ref "U$2") (pin "D+") (pinfunction "D+_D+") (pintype "bidirectional"))
    )
    (net (code "78") (name "VBAT") (class "Default")
      (node (ref "C26") (pin "1") (pinfunction "1_1") (pintype "passive"))
      (node (ref "C27") (pin "1") (pinfunction "1_1") (pintype "passive"))
      (node (ref "C28") (pin "1") (pinfunction "1_1") (pintype "passive"))
      (node (ref "C29") (pin "1") (pinfunction "1_1") (pintype "passive"))
      (node (ref "C32") (pin "1") (pinfunction "1_1") (pintype "passive"))
      (node (ref "C33") (pin "1") (pinfunction "1_1") (pintype "passive"))
      (node (ref "C4") (pin "1") (pinfunction "1_1") (pintype "passive"))
      (node (ref "IC1") (pin "8") (pinfunction "VCC_8") (pintype "power_in"))
      (node (ref "IC2") (pin "4") (pinfunction "VIN_4") (pintype "bidirectional"))
      (node (ref "IC5") (pin "1") (pinfunction "VDD_1") (pintype "power_in"))
      (node (ref "IC6") (pin "1") (pinfunction "VDD_1") (pintype "power_in"))
      (node (ref "IC7") (pin "1") (pinfunction "VDD_1") (pintype "power_in"))
      (node (ref "IC8") (pin "1") (pinfunction "VDD_1") (pintype "power_in"))
      (node (ref "OFF/ON") (pin "3") (pinfunction "S_3") (pintype "passive"))
      (node (ref "R16") (pin "2") (pinfunction "2_2") (pintype "passive"))
      (node (ref "RESETTABLE_FUSE") (pin "2") (pinfunction "2_2") (pintype "passive"))
    )
    (net (code "79") (name "VCC") (class "Default")
      (node (ref "C1") (pin "1") (pinfunction "1_1") (pintype "passive"))
      (node (ref "C11") (pin "1") (pinfunction "1_1") (pintype "passive"))
      (node (ref "C14") (pin "1") (pinfunction "1_1") (pintype "passive"))
      (node (ref "C15") (pin "1") (pinfunction "1_1") (pintype "passive"))
      (node (ref "C16") (pin "1") (pinfunction "1_1") (pintype "passive"))
      (node (ref "C3") (pin "1") (pinfunction "1_1") (pintype "passive"))
      (node (ref "C35") (pin "1") (pinfunction "1_1") (pintype "passive"))
      (node (ref "C5") (pin "1") (pinfunction "1_1") (pintype "passive"))
      (node (ref "C8") (pin "1") (pinfunction "1_1") (pintype "passive"))
      (node (ref "D1") (pin "A") (pinfunction "A_A") (pintype "passive"))
      (node (ref "EMIFILTER1") (pin "1") (pinfunction "IN/OUT_1") (pintype "bidirectional"))
      (node (ref "EMIFILTER2") (pin "1") (pinfunction "IN/OUT_1") (pintype "bidirectional"))
      (node (ref "IC2") (pin "1") (pinfunction "VOUT_1") (pintype "bidirectional"))
      (node (ref "IC3") (pin "20") (pinfunction "VCCIO_1_20") (pintype "bidirectional"))
      (node (ref "IC3") (pin "31") (pinfunction "VCCIO_2_31") (pintype "bidirectional"))
      (node (ref "IC3") (pin "42") (pinfunction "VCCIO_3_42") (pintype "bidirectional"))
      (node (ref "IC3") (pin "50") (pinfunction "VREGIN_50") (pintype "bidirectional"))
      (node (ref "IC3") (pin "56") (pinfunction "VCCIO_4_56") (pintype "bidirectional"))
      (node (ref "IC4") (pin "6") (pinfunction "VCC_6") (pintype "power_in"))
      (node (ref "J1") (pin "1") (pinfunction "1_1") (pintype "passive"))
      (node (ref "J2") (pin "6") (pinfunction "6_6") (pintype "passive"))
      (node (ref "R1") (pin "2") (pinfunction "2_2") (pintype "passive"))
      (node (ref "R11") (pin "2") (pinfunction "2_2") (pintype "passive"))
      (node (ref "R12") (pin "2") (pinfunction "2_2") (pintype "passive"))
      (node (ref "R15") (pin "1") (pinfunction "1_1") (pintype "passive"))
      (node (ref "R18") (pin "1") (pinfunction "1_1") (pintype "passive"))
      (node (ref "R4") (pin "2") (pinfunction "2_2") (pintype "passive"))
      (node (ref "R5") (pin "1") (pinfunction "1_1") (pintype "passive"))
      (node (ref "R7") (pin "2") (pinfunction "2_2") (pintype "passive"))
      (node (ref "R8") (pin "1") (pinfunction "1_1") (pintype "passive"))
      (node (ref "R9") (pin "2") (pinfunction "2_2") (pintype "passive"))
      (node (ref "U$1") (pin "VCC") (pinfunction "VCC_VCC") (pintype "power_in"))
      (node (ref "U2") (pin "2") (pinfunction "3V3_2") (pintype "bidirectional"))
    )
    (net (code "80") (name "VCC1.8") (class "Default")
      (node (ref "C10") (pin "1") (pinfunction "1_1") (pintype "passive"))
      (node (ref "C12") (pin "1") (pinfunction "1_1") (pintype "passive"))
      (node (ref "C17") (pin "1") (pinfunction "1_1") (pintype "passive"))
      (node (ref "C9") (pin "1") (pinfunction "1_1") (pintype "passive"))
      (node (ref "IC3") (pin "12") (pinfunction "VCORE_1_12") (pintype "bidirectional"))
      (node (ref "IC3") (pin "37") (pinfunction "VCORE_2_37") (pintype "bidirectional"))
      (node (ref "IC3") (pin "49") (pinfunction "VREGOUT_49") (pintype "bidirectional"))
      (node (ref "IC3") (pin "64") (pinfunction "VCORE_3_64") (pintype "bidirectional"))
    )
    (net (code "81") (name "VCC5V") (class "Default")
      (node (ref "C13") (pin "2") (pinfunction "2_2") (pintype "passive"))
      (node (ref "IC-IP5305") (pin "VIN") (pinfunction "1_VIN") (pintype "power_in"))
      (node (ref "R2") (pin "1") (pinfunction "1_1") (pintype "passive"))
      (node (ref "U$2") (pin "+5V") (pinfunction "+5V_+5V") (pintype "bidirectional"))
    )
    (net (code "82") (name "unconnected-(IC2-ADJ-Pad8)") (class "Default")
      (node (ref "IC2") (pin "8") (pinfunction "ADJ_8") (pintype "bidirectional"))
    )
    (net (code "83") (name "unconnected-(IC3-ACBUS0-Pad26)") (class "Default")
      (node (ref "IC3") (pin "26") (pinfunction "ACBUS0_26") (pintype "bidirectional"))
    )
    (net (code "84") (name "unconnected-(IC3-ACBUS1-Pad27)") (class "Default")
      (node (ref "IC3") (pin "27") (pinfunction "ACBUS1_27") (pintype "bidirectional"))
    )
    (net (code "85") (name "unconnected-(IC3-ACBUS2-Pad28)") (class "Default")
      (node (ref "IC3") (pin "28") (pinfunction "ACBUS2_28") (pintype "bidirectional"))
    )
    (net (code "86") (name "unconnected-(IC3-ACBUS3-Pad29)") (class "Default")
      (node (ref "IC3") (pin "29") (pinfunction "ACBUS3_29") (pintype "bidirectional"))
    )
    (net (code "87") (name "unconnected-(IC3-ACBUS4-Pad30)") (class "Default")
      (node (ref "IC3") (pin "30") (pinfunction "ACBUS4_30") (pintype "bidirectional"))
    )
    (net (code "88") (name "unconnected-(IC3-ACBUS5-Pad32)") (class "Default")
      (node (ref "IC3") (pin "32") (pinfunction "ACBUS5_32") (pintype "bidirectional"))
    )
    (net (code "89") (name "unconnected-(IC3-ACBUS6-Pad33)") (class "Default")
      (node (ref "IC3") (pin "33") (pinfunction "ACBUS6_33") (pintype "bidirectional"))
    )
    (net (code "90") (name "unconnected-(IC3-ACBUS7-Pad34)") (class "Default")
      (node (ref "IC3") (pin "34") (pinfunction "ACBUS7_34") (pintype "bidirectional"))
    )
    (net (code "91") (name "unconnected-(IC3-ADBUS4-Pad21)") (class "Default")
      (node (ref "IC3") (pin "21") (pinfunction "ADBUS4_21") (pintype "bidirectional"))
    )
    (net (code "92") (name "unconnected-(IC3-ADBUS5-Pad22)") (class "Default")
      (node (ref "IC3") (pin "22") (pinfunction "ADBUS5_22") (pintype "bidirectional"))
    )
    (net (code "93") (name "unconnected-(IC3-ADBUS6-Pad23)") (class "Default")
      (node (ref "IC3") (pin "23") (pinfunction "ADBUS6_23") (pintype "bidirectional"))
    )
    (net (code "94") (name "unconnected-(IC3-ADBUS7-Pad24)") (class "Default")
      (node (ref "IC3") (pin "24") (pinfunction "ADBUS7_24") (pintype "bidirectional"))
    )
    (net (code "95") (name "unconnected-(IC3-BCBUS0-Pad48)") (class "Default")
      (node (ref "IC3") (pin "48") (pinfunction "BCBUS0_48") (pintype "bidirectional"))
    )
    (net (code "96") (name "unconnected-(IC3-BCBUS1-Pad52)") (class "Default")
      (node (ref "IC3") (pin "52") (pinfunction "BCBUS1_52") (pintype "bidirectional"))
    )
    (net (code "97") (name "unconnected-(IC3-BCBUS2-Pad53)") (class "Default")
      (node (ref "IC3") (pin "53") (pinfunction "BCBUS2_53") (pintype "bidirectional"))
    )
    (net (code "98") (name "unconnected-(IC3-BCBUS5-Pad57)") (class "Default")
      (node (ref "IC3") (pin "57") (pinfunction "BCBUS5_57") (pintype "bidirectional"))
    )
    (net (code "99") (name "unconnected-(IC3-BCBUS6-Pad58)") (class "Default")
      (node (ref "IC3") (pin "58") (pinfunction "BCBUS6_58") (pintype "bidirectional"))
    )
    (net (code "100") (name "unconnected-(IC3-BDBUS4-Pad43)") (class "Default")
      (node (ref "IC3") (pin "43") (pinfunction "BDBUS4_43") (pintype "bidirectional"))
    )
    (net (code "101") (name "unconnected-(IC3-BDBUS5-Pad44)") (class "Default")
      (node (ref "IC3") (pin "44") (pinfunction "BDBUS5_44") (pintype "bidirectional"))
    )
    (net (code "102") (name "unconnected-(IC3-BDBUS6-Pad45)") (class "Default")
      (node (ref "IC3") (pin "45") (pinfunction "BDBUS6_45") (pintype "bidirectional"))
    )
    (net (code "103") (name "unconnected-(IC3-BDBUS7-Pad46)") (class "Default")
      (node (ref "IC3") (pin "46") (pinfunction "BDBUS7_46") (pintype "bidirectional"))
    )
    (net (code "104") (name "unconnected-(IC8-DOUT-Pad2)") (class "Default")
      (node (ref "IC8") (pin "2") (pinfunction "DOUT_2") (pintype "output"))
    )
    (net (code "105") (name "unconnected-(U$1-NC_1-PadNC1)") (class "Default")
      (node (ref "U$1") (pin "NC1") (pinfunction "NC_1_NC1") (pintype "no_connect"))
    )
    (net (code "106") (name "unconnected-(U$1-NC_2-PadNC2)") (class "Default")
      (node (ref "U$1") (pin "NC2") (pinfunction "NC_2_NC2") (pintype "no_connect"))
    )
    (net (code "107") (name "unconnected-(U$1-NC_3-PadNC3)") (class "Default")
      (node (ref "U$1") (pin "NC3") (pinfunction "NC_3_NC3") (pintype "no_connect"))
    )
    (net (code "108") (name "unconnected-(U$1-NC_4-PadNC4)") (class "Default")
      (node (ref "U$1") (pin "NC4") (pinfunction "NC_4_NC4") (pintype "no_connect"))
    )
    (net (code "109") (name "unconnected-(U$2-PadID)") (class "Default")
      (node (ref "U$2") (pin "ID") (pinfunction "ID_ID") (pintype "bidirectional"))
    )
    (net (code "110") (name "unconnected-(U2-CLK-Pad20)") (class "Default")
      (node (ref "U2") (pin "20") (pinfunction "CLK_20") (pintype "bidirectional"))
    )
    (net (code "111") (name "unconnected-(U2-CMD-Pad19)") (class "Default")
      (node (ref "U2") (pin "19") (pinfunction "CMD_19") (pintype "bidirectional"))
    )
    (net (code "112") (name "unconnected-(U2-NC-Pad32)") (class "Default")
      (node (ref "U2") (pin "32") (pinfunction "NC_32") (pintype "bidirectional"))
    )
    (net (code "113") (name "unconnected-(U2-SD1-Pad22)") (class "Default")
      (node (ref "U2") (pin "22") (pinfunction "SD1_22") (pintype "bidirectional"))
    )
    (net (code "114") (name "unconnected-(U2-SD2-Pad17)") (class "Default")
      (node (ref "U2") (pin "17") (pinfunction "SD2_17") (pintype "bidirectional"))
    )
    (net (code "115") (name "unconnected-(U2-SD3-Pad18)") (class "Default")
      (node (ref "U2") (pin "18") (pinfunction "SD3_18") (pintype "bidirectional"))
    )
    (net (code "116") (name "unconnected-(U2-SDO-Pad21)") (class "Default")
      (node (ref "U2") (pin "21") (pinfunction "SDO_21") (pintype "bidirectional"))
    )
  )
)
